# pH_to_I2C_v20.net
KiCad netlist of a schematic drawn in EAGLE
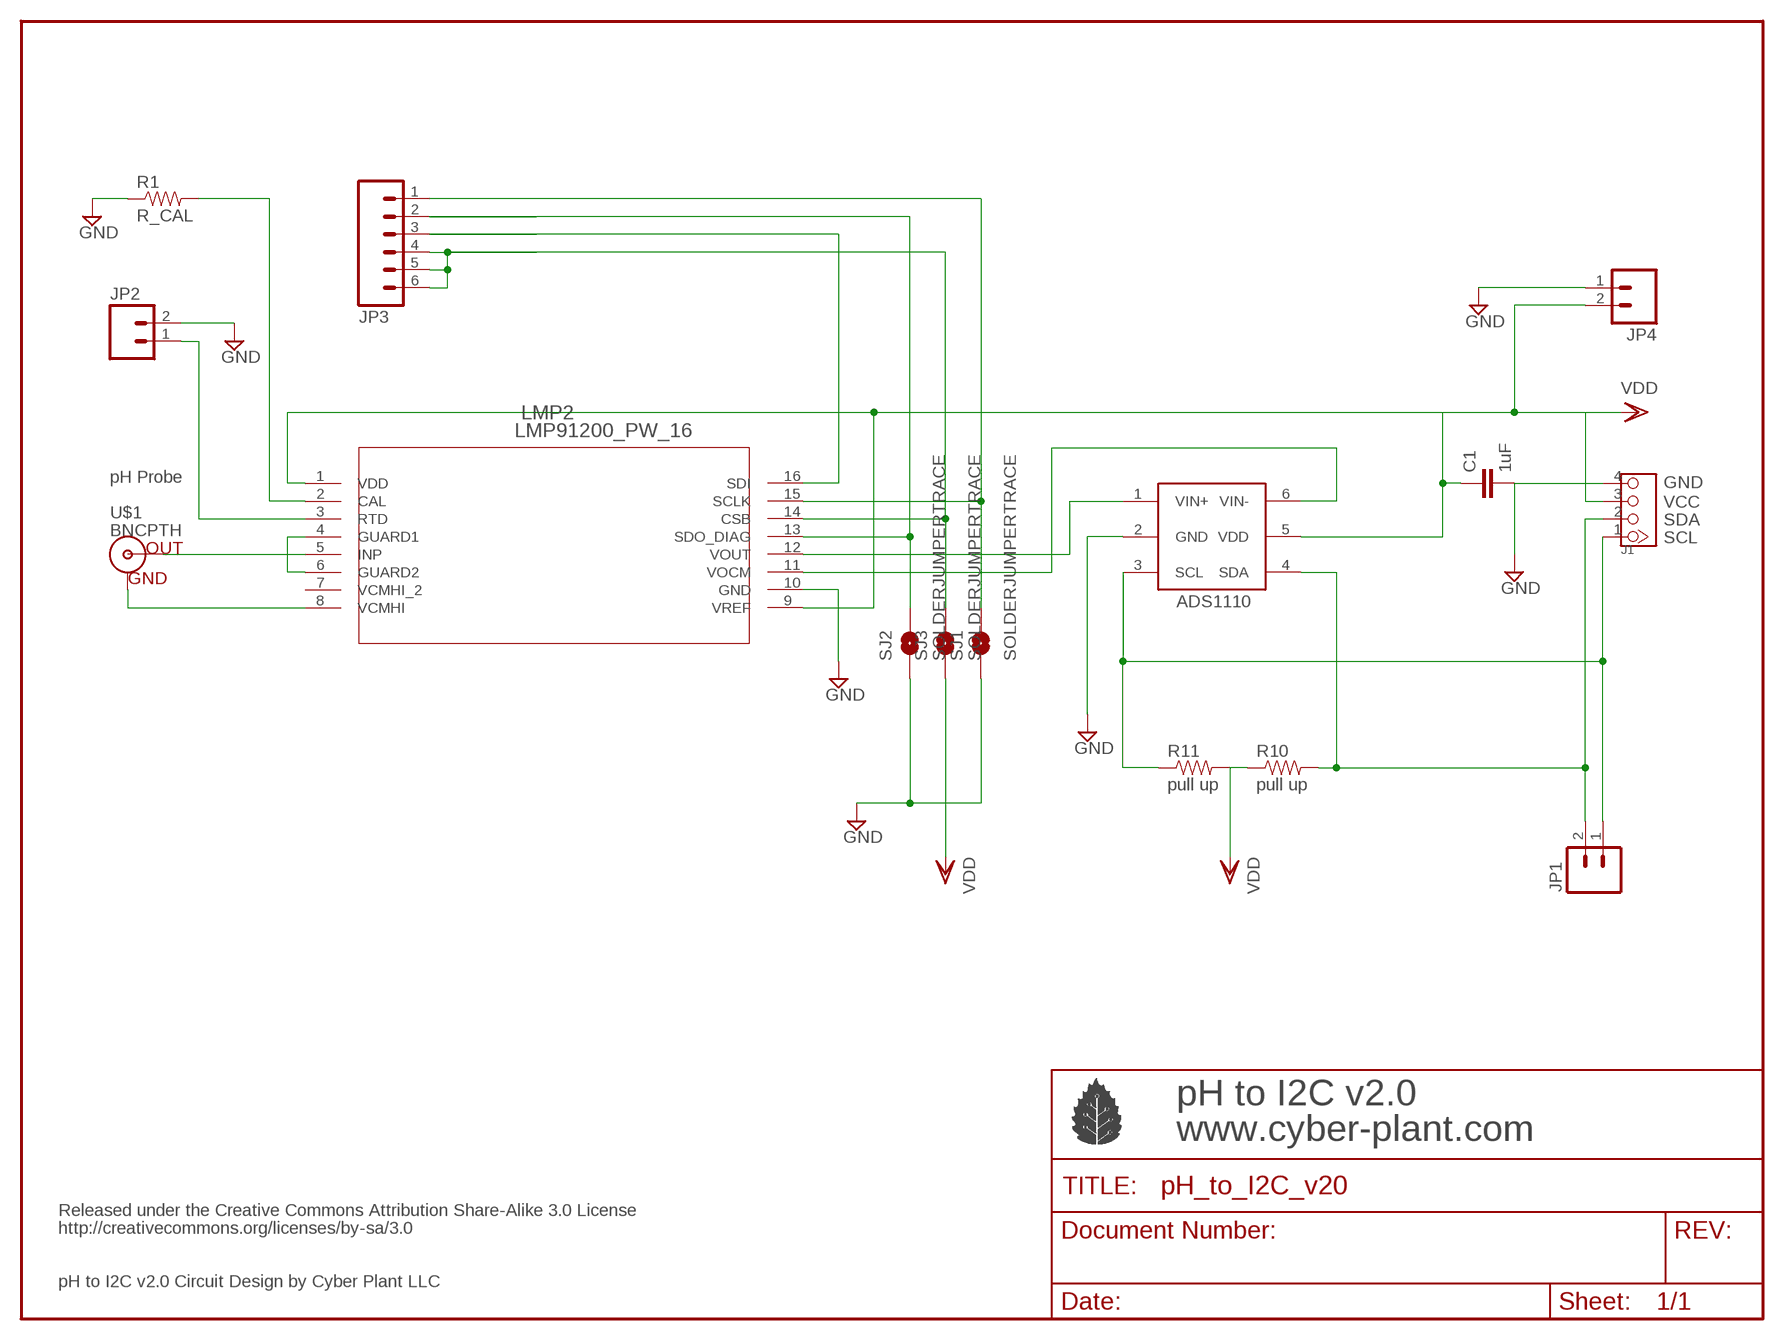
[diagram p0: schematic, sheet 1]

(export (version "E")
  (design (tool "Eeschema 10.0.6"))
  (components
    (comp (ref "C1")
      (value "1uF")
      (footprint "eagle-import:1206")
      (libsource (lib "eagle-import") (part "CAP1206"))
    )
    (comp (ref "IC1")
      (value "ADS1110")
      (footprint "eagle-import:SOT-23-6")
      (libsource (lib "eagle-import") (part "ADS1110"))
    )
    (comp (ref "J1")
      (value "TWIG-4P-2.090D")
      (footprint "eagle-import:4P-2.0-90D")
      (libsource (lib "eagle-import") (part "TWIG-4P-2.090D"))
    )
    (comp (ref "JP1")
      (value "M02PTH")
      (footprint "eagle-import:1X02")
      (libsource (lib "eagle-import") (part "M02PTH"))
    )
    (comp (ref "JP2")
      (value "M02PTH")
      (footprint "eagle-import:1X02")
      (libsource (lib "eagle-import") (part "M02PTH"))
    )
    (comp (ref "JP3")
      (value "M06SIP")
      (footprint "eagle-import:1X06")
      (libsource (lib "eagle-import") (part "M06SIP"))
    )
    (comp (ref "JP4")
      (value "M02PTH")
      (footprint "eagle-import:1X02")
      (libsource (lib "eagle-import") (part "M02PTH"))
    )
    (comp (ref "LMP2")
      (value "LMP91200_PW_16")
      (footprint "eagle-import:MTC16")
      (fields
        (field (name "MANUFACTURER") "Texas Instruments")
        (field (name "MANUFACTURER_PART_NUMBER") "lmp91200_pw_16")
      )
      (libsource (lib "eagle-import") (part "LMP91200_PW_16"))
    )
    (comp (ref "R1")
      (value "R_CAL")
      (footprint "eagle-import:AXIAL-0.4")
      (libsource (lib "eagle-import") (part "RESISTORPTH-1/4W"))
    )
    (comp (ref "R10")
      (value "pull up")
      (footprint "eagle-import:AXIAL-0.4")
      (libsource (lib "eagle-import") (part "RESISTORPTH-1/4W"))
    )
    (comp (ref "R11")
      (value "pull up")
      (footprint "eagle-import:AXIAL-0.4")
      (libsource (lib "eagle-import") (part "RESISTORPTH-1/4W"))
    )
    (comp (ref "SJ1")
      (value "SOLDERJUMPERTRACE")
      (footprint "eagle-import:SJ_2S-TRACE")
      (libsource (lib "eagle-import") (part "SOLDERJUMPERTRACE"))
    )
    (comp (ref "SJ2")
      (value "SOLDERJUMPERTRACE")
      (footprint "eagle-import:SJ_2S-TRACE")
      (libsource (lib "eagle-import") (part "SOLDERJUMPERTRACE"))
    )
    (comp (ref "SJ3")
      (value "SOLDERJUMPERTRACE")
      (footprint "eagle-import:SJ_2S-TRACE")
      (libsource (lib "eagle-import") (part "SOLDERJUMPERTRACE"))
    )
    (comp (ref "U$1")
      (value "BNCPTH")
      (footprint "eagle-import:BNC")
      (libsource (lib "eagle-import") (part "BNCPTH"))
    )
  )
  (nets
    (net (code "1") (name "GND") (class "Default")
      (node (ref "C1") (pin "2") (pinfunction "2_2") (pintype "passive"))
      (node (ref "IC1") (pin "2") (pinfunction "GND_2") (pintype "bidirectional"))
      (node (ref "J1") (pin "4") (pinfunction "4_4") (pintype "bidirectional"))
      (node (ref "JP2") (pin "2") (pinfunction "2_2") (pintype "passive"))
      (node (ref "JP4") (pin "1") (pinfunction "1_1") (pintype "passive"))
      (node (ref "LMP2") (pin "10") (pinfunction "GND_10") (pintype "power_in"))
      (node (ref "R1") (pin "P$1") (pinfunction "1_P$1") (pintype "passive"))
      (node (ref "SJ1") (pin "1") (pinfunction "1_1") (pintype "passive"))
      (node (ref "SJ2") (pin "1") (pinfunction "1_1") (pintype "passive"))
    )
    (net (code "2") (name "Net-(IC1-SCL)") (class "Default")
      (node (ref "IC1") (pin "3") (pinfunction "SCL_3") (pintype "bidirectional"))
      (node (ref "J1") (pin "1") (pinfunction "1_1") (pintype "bidirectional"))
      (node (ref "JP1") (pin "1") (pinfunction "1_1") (pintype "passive"))
      (node (ref "R11") (pin "P$1") (pinfunction "1_P$1") (pintype "passive"))
    )
    (net (code "3") (name "Net-(IC1-SDA)") (class "Default")
      (node (ref "IC1") (pin "4") (pinfunction "SDA_4") (pintype "bidirectional"))
      (node (ref "J1") (pin "2") (pinfunction "2_2") (pintype "bidirectional"))
      (node (ref "JP1") (pin "2") (pinfunction "2_2") (pintype "passive"))
      (node (ref "R10") (pin "P$2") (pinfunction "2_P$2") (pintype "passive"))
    )
    (net (code "4") (name "Net-(IC1-VIN+)") (class "Default")
      (node (ref "IC1") (pin "1") (pinfunction "VIN+_1") (pintype "bidirectional"))
      (node (ref "LMP2") (pin "12") (pinfunction "VOUT_12") (pintype "output"))
    )
    (net (code "5") (name "Net-(IC1-VIN-)") (class "Default")
      (node (ref "IC1") (pin "6") (pinfunction "VIN-_6") (pintype "bidirectional"))
      (node (ref "LMP2") (pin "11") (pinfunction "VOCM_11") (pintype "output"))
    )
    (net (code "6") (name "Net-(LMP2-CAL)") (class "Default")
      (node (ref "LMP2") (pin "2") (pinfunction "CAL_2") (pintype "passive"))
      (node (ref "R1") (pin "P$2") (pinfunction "2_P$2") (pintype "passive"))
    )
    (net (code "7") (name "Net-(LMP2-CSB)") (class "Default")
      (node (ref "JP3") (pin "4") (pinfunction "4_4") (pintype "passive"))
      (node (ref "JP3") (pin "5") (pinfunction "5_5") (pintype "passive"))
      (node (ref "JP3") (pin "6") (pinfunction "6_6") (pintype "passive"))
      (node (ref "LMP2") (pin "14") (pinfunction "CSB_14") (pintype "passive"))
      (node (ref "SJ3") (pin "2") (pinfunction "2_2") (pintype "passive"))
    )
    (net (code "8") (name "Net-(LMP2-GUARD1)") (class "Default")
      (node (ref "LMP2") (pin "4") (pinfunction "GUARD1_4") (pintype "passive"))
      (node (ref "LMP2") (pin "6") (pinfunction "GUARD2_6") (pintype "passive"))
    )
    (net (code "9") (name "Net-(LMP2-INP)") (class "Default")
      (node (ref "LMP2") (pin "5") (pinfunction "INP_5") (pintype "input"))
      (node (ref "U$1") (pin "S") (pinfunction "OUT_S") (pintype "bidirectional"))
    )
    (net (code "10") (name "Net-(LMP2-RTD)") (class "Default")
      (node (ref "JP2") (pin "1") (pinfunction "1_1") (pintype "passive"))
      (node (ref "LMP2") (pin "3") (pinfunction "RTD_3") (pintype "bidirectional"))
    )
    (net (code "11") (name "Net-(LMP2-SCLK)") (class "Default")
      (node (ref "JP3") (pin "1") (pinfunction "1_1") (pintype "passive"))
      (node (ref "LMP2") (pin "15") (pinfunction "SCLK_15") (pintype "passive"))
      (node (ref "SJ1") (pin "2") (pinfunction "2_2") (pintype "passive"))
    )
    (net (code "12") (name "Net-(LMP2-SDI)") (class "Default")
      (node (ref "JP3") (pin "3") (pinfunction "3_3") (pintype "passive"))
      (node (ref "LMP2") (pin "16") (pinfunction "SDI_16") (pintype "passive"))
    )
    (net (code "13") (name "Net-(LMP2-SDO_DIAG)") (class "Default")
      (node (ref "JP3") (pin "2") (pinfunction "2_2") (pintype "passive"))
      (node (ref "LMP2") (pin "13") (pinfunction "SDO_DIAG_13") (pintype "bidirectional"))
      (node (ref "SJ2") (pin "2") (pinfunction "2_2") (pintype "passive"))
    )
    (net (code "14") (name "Net-(LMP2-VCMHI)") (class "Default")
      (node (ref "LMP2") (pin "8") (pinfunction "VCMHI_8") (pintype "output"))
      (node (ref "U$1") (pin "GND") (pinfunction "GND_GND") (pintype "bidirectional"))
    )
    (net (code "15") (name "VDD") (class "Default")
      (node (ref "C1") (pin "1") (pinfunction "1_1") (pintype "passive"))
      (node (ref "IC1") (pin "5") (pinfunction "VDD_5") (pintype "bidirectional"))
      (node (ref "J1") (pin "3") (pinfunction "3_3") (pintype "bidirectional"))
      (node (ref "JP4") (pin "2") (pinfunction "2_2") (pintype "passive"))
      (node (ref "LMP2") (pin "1") (pinfunction "VDD_1") (pintype "power_in"))
      (node (ref "LMP2") (pin "9") (pinfunction "VREF_9") (pintype "input"))
      (node (ref "R10") (pin "P$1") (pinfunction "1_P$1") (pintype "passive"))
      (node (ref "R11") (pin "P$2") (pinfunction "2_P$2") (pintype "passive"))
      (node (ref "SJ3") (pin "1") (pinfunction "1_1") (pintype "passive"))
    )
    (net (code "16") (name "unconnected-(LMP2-VCMHI_2-Pad7)") (class "Default")
      (node (ref "LMP2") (pin "7") (pinfunction "VCMHI_2_7") (pintype "output"))
    )
  )
)
